# Controlador_de_corriente_V3.net
KiCad netlist of a schematic drawn in Altium Designer
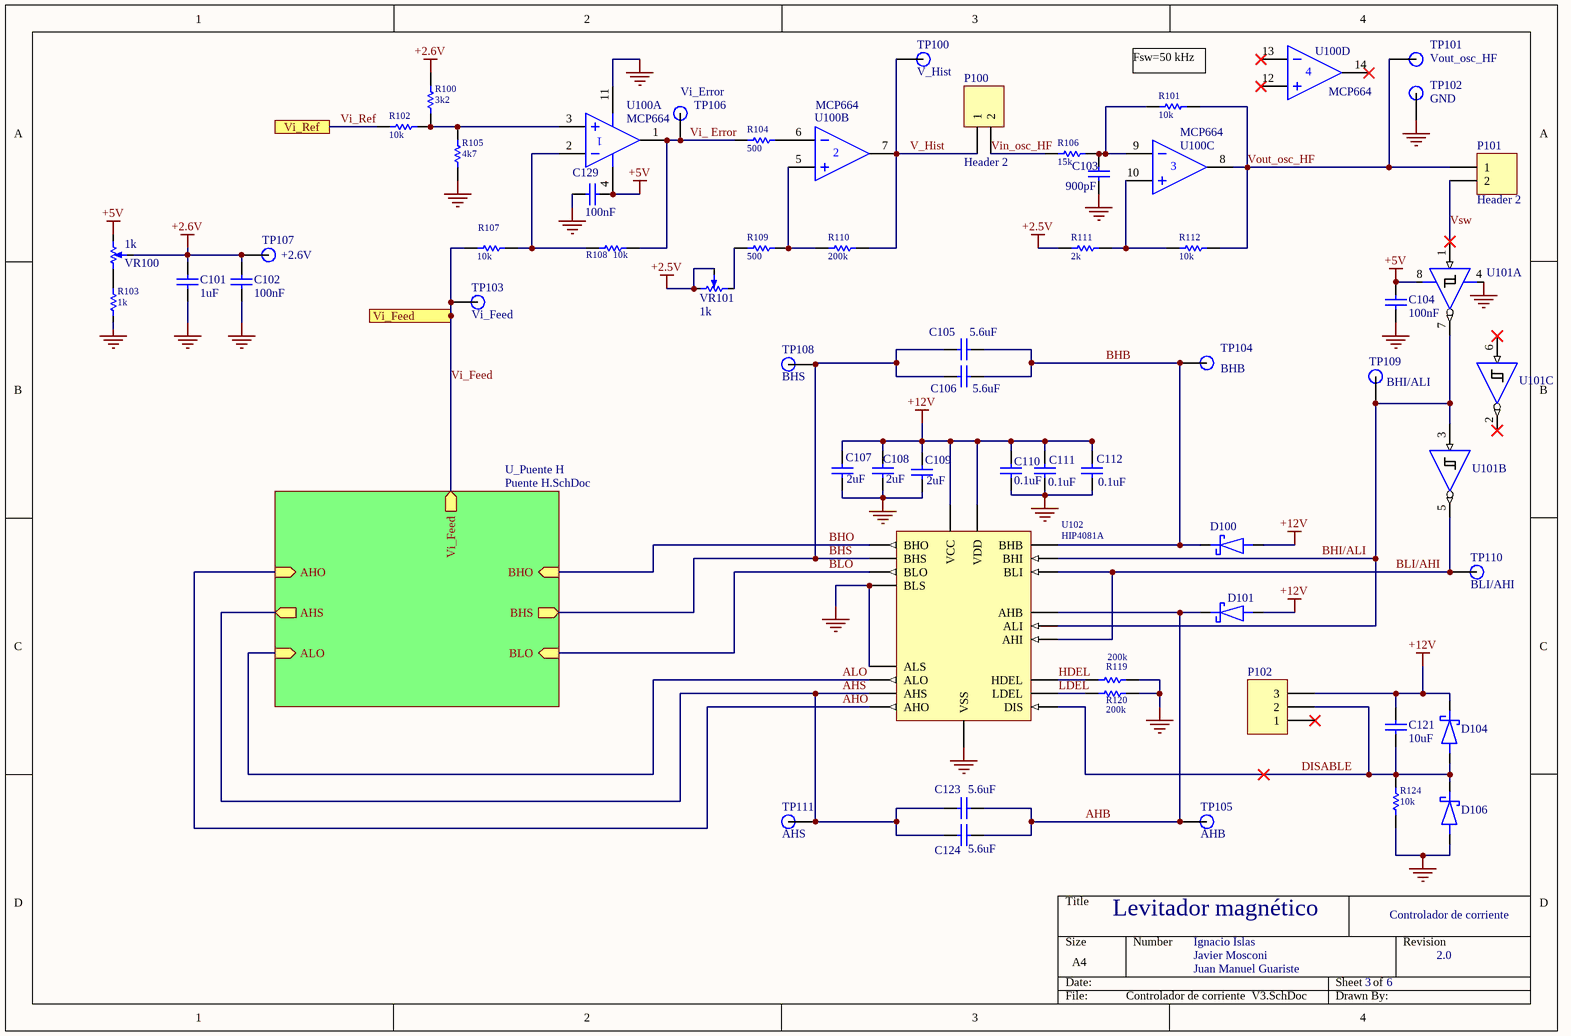
[diagram p0: Controlador de corriente  V3.SchDoc]

(export (version "E")
  (design (tool "Eeschema 10.0.6"))
  (components
    (comp (ref "C101")
      (value "1uF")
      (footprint "C1206")
      (description "CAP CER 1UF 25V X7R 1206")
      (fields (field (name "MANUFACTURER") "CAL-CHIP ELECTRONICS, INC.") (field (name "Comment") "Capacitor"))
      (libsource (lib "Levitador_GMI") (part "Capacitor"))
    )
    (comp (ref "C102")
      (value "100nF")
      (footprint "C1206")
      (description "CAP CER 0.1UF 50V X7R 1206")
      (fields (field (name "MANUFACTURER") "Venkel") (field (name "Comment") "Capacitor"))
      (libsource (lib "Levitador_GMI") (part "Capacitor"))
    )
    (comp (ref "C103")
      (value "900pF")
      (footprint "C1206")
      (description "CAP CER 910PF 50V NP0 1206")
      (fields (field (name "MANUFACTURER") "KEMET") (field (name "Comment") "Capacitor"))
      (libsource (lib "Levitador_GMI") (part "Capacitor"))
    )
    (comp (ref "C104")
      (value "100nF")
      (footprint "C1206")
      (description "CAP CER 0.1UF 50V X7R 1206")
      (fields (field (name "MANUFACTURER") "Venkel") (field (name "Comment") "Capacitor"))
      (libsource (lib "Levitador_GMI") (part "Capacitor"))
    )
    (comp (ref "C105")
      (value "5.6uF")
      (footprint "C1206")
      (description "CAP CER 4.7UF 50V X7R 1206")
      (fields (field (name "MANUFACTURER") "Samsung Electro-Mechanics") (field (name "Comment") "Capacitor"))
      (libsource (lib "Levitador_GMI") (part "Capacitor"))
    )
    (comp (ref "C106")
      (value "5.6uF")
      (footprint "C1206")
      (description "CAP CER 4.7UF 50V X7R 1206")
      (fields (field (name "MANUFACTURER") "Samsung Electro-Mechanics") (field (name "Comment") "Capacitor"))
      (libsource (lib "Levitador_GMI") (part "Capacitor"))
    )
    (comp (ref "C107")
      (value "2uF")
      (footprint "C1206")
      (description "CAP1206 X5R 2.2UF 20% 35V")
      (fields (field (name "MANUFACTURER") "CAL-CHIP ELECTRONICS, INC.") (field (name "Comment") "Capacitor"))
      (libsource (lib "Levitador_GMI") (part "Capacitor"))
    )
    (comp (ref "C108")
      (value "2uF")
      (footprint "C1206")
      (description "CAP1206 X5R 2.2UF 20% 35V")
      (fields (field (name "MANUFACTURER") "CAL-CHIP ELECTRONICS, INC.") (field (name "Comment") "Capacitor"))
      (libsource (lib "Levitador_GMI") (part "Capacitor"))
    )
    (comp (ref "C109")
      (value "2uF")
      (footprint "C1206")
      (description "CAP1206 X5R 2.2UF 20% 35V")
      (fields (field (name "MANUFACTURER") "CAL-CHIP ELECTRONICS, INC.") (field (name "Comment") "Capacitor"))
      (libsource (lib "Levitador_GMI") (part "Capacitor"))
    )
    (comp (ref "C110")
      (value "0.1uF")
      (footprint "C1206")
      (description "CAP CER 0.1UF 50V X7R 1206")
      (fields (field (name "MANUFACTURER") "Venkel") (field (name "Comment") "Capacitor"))
      (libsource (lib "Levitador_GMI") (part "Capacitor"))
    )
    (comp (ref "C111")
      (value "0.1uF")
      (footprint "C1206")
      (description "CAP CER 0.1UF 50V X7R 1206")
      (fields (field (name "MANUFACTURER") "Venkel") (field (name "Comment") "Capacitor"))
      (libsource (lib "Levitador_GMI") (part "Capacitor"))
    )
    (comp (ref "C112")
      (value "0.1uF")
      (footprint "C1206")
      (description "CAP CER 0.1UF 50V X7R 1206")
      (fields (field (name "MANUFACTURER") "Venkel") (field (name "Comment") "Capacitor"))
      (libsource (lib "Levitador_GMI") (part "Capacitor"))
    )
    (comp (ref "C121")
      (value "10uF")
      (footprint "C1206")
      (description "CAP CER 10UF 16V X7R 1206")
      (fields (field (name "MANUFACTURER") "CAL-CHIP ELECTRONICS, INC.") (field (name "Comment") "Capacitor"))
      (libsource (lib "Levitador_GMI") (part "Capacitor"))
    )
    (comp (ref "C123")
      (value "5.6uF")
      (footprint "C1206")
      (description "CAP CER 4.7UF 50V X7R 1206")
      (fields (field (name "MANUFACTURER") "Samsung Electro-Mechanics") (field (name "Comment") "Capacitor"))
      (libsource (lib "Levitador_GMI") (part "Capacitor"))
    )
    (comp (ref "C124")
      (value "5.6uF")
      (footprint "C1206")
      (description "CAP CER 4.7UF 50V X7R 1206")
      (fields (field (name "MANUFACTURER") "Samsung Electro-Mechanics") (field (name "Comment") "Capacitor"))
      (libsource (lib "Levitador_GMI") (part "Capacitor"))
    )
    (comp (ref "C129")
      (value "100nF")
      (footprint "C1206")
      (description "CAP CER 0.1UF 50V X7R 1206")
      (fields (field (name "MANUFACTURER") "Venkel") (field (name "Comment") "Capacitor"))
      (libsource (lib "Levitador_GMI") (part "Capacitor"))
    )
    (comp (ref "D100")
      (value "RSX205LAM30TR")
      (footprint "SODFL4725X105N")
      (description "DIODE SCHOTTKY 30V 2A PMDTM")
      (libsource (lib "Levitador_GMI") (part "RSX205LAM30TR"))
    )
    (comp (ref "D101")
      (value "RSX205LAM30TR")
      (footprint "SODFL4725X105N")
      (description "DIODE SCHOTTKY 30V 2A PMDTM")
      (libsource (lib "Levitador_GMI") (part "RSX205LAM30TR"))
    )
    (comp (ref "D104")
      (value "RSX205LAM30TR")
      (footprint "SODFL4725X105N")
      (description "DIODE SCHOTTKY 30V 2A PMDTM")
      (libsource (lib "Levitador_GMI") (part "RSX205LAM30TR"))
    )
    (comp (ref "D106")
      (value "RSX205LAM30TR")
      (footprint "SODFL4725X105N")
      (description "DIODE SCHOTTKY 30V 2A PMDTM")
      (libsource (lib "Levitador_GMI") (part "RSX205LAM30TR"))
    )
    (comp (ref "P100")
      (value "Header 2")
      (footprint "HDR1X2")
      (description "TERM BLK 2P SIDE ENT 2.54MM PCB")
      (fields (field (name "MANUFACTURER") "TE Connectivity AMP Connectors"))
      (libsource (lib "") (part "Header 2_1"))
    )
    (comp (ref "P101")
      (value "Header 2")
      (footprint "HDR1X2")
      (description "TERM BLK 2P SIDE ENT 2.54MM PCB")
      (fields (field (name "MANUFACTURER") "TE Connectivity AMP Connectors"))
      (libsource (lib "Levitador_GMI") (part "Header 2"))
    )
    (comp (ref "P102")
      (value "Header 3")
      (footprint "HDR1X3")
      (description "TERM BLK 3P SIDE ENT 2.54MM PCB")
      (fields (field (name "MANUFACTURER") "TE Connectivity AMP Connectors"))
      (libsource (lib "Levitador_GMI") (part "Header 3"))
    )
    (comp (ref "R100")
      (value "3k2")
      (footprint "Levitador_GMI:R1206")
      (description "RES 3.2K OHM 1% 1/4W 1206")
      (fields (field (name "MANUFACTURER") "KOA Speer Electronics, Inc.") (field (name "TOLERANCE") "1%"))
      (libsource (lib "Levitador_GMI") (part "R1206"))
    )
    (comp (ref "R101")
      (value "10k")
      (footprint "Levitador_GMI:R1206")
      (description "RES 10K OHM 1% 1/4W 1206")
      (fields (field (name "MANUFACTURER") "YAGEO") (field (name "TOLERANCE") "1%"))
      (libsource (lib "Levitador_GMI") (part "R1206"))
    )
    (comp (ref "R102")
      (value "10k")
      (footprint "Levitador_GMI:R1206")
      (description "RES 10K OHM 1% 1/4W 1206")
      (fields (field (name "MANUFACTURER") "YAGEO") (field (name "TOLERANCE") "1%"))
      (libsource (lib "Levitador_GMI") (part "R1206"))
    )
    (comp (ref "R103")
      (value "1k")
      (footprint "Levitador_GMI:R1206")
      (description "Resistor Chip; 1/8W;")
      (fields (field (name "MANUFACTURER") "Stackpole Electronics Inc") (field (name "TOLERANCE") "1%"))
      (libsource (lib "Levitador_GMI") (part "R1206"))
    )
    (comp (ref "R104")
      (value "500")
      (footprint "Levitador_GMI:R1206")
      (description "RES SMD 500 OHM 0.1% 0.3W 1206")
      (fields
        (field (name "MANUFACTURER") "Vishay Foil Resistors (Division of Vishay Precision Group)")
        (field (name "TOLERANCE") "0.1%")
      )
      (libsource (lib "Levitador_GMI") (part "R1206"))
    )
    (comp (ref "R105")
      (value "4k7")
      (footprint "Levitador_GMI:R1206")
      (description "RES 4.7K OHM 1% 1/4W 1206")
      (fields (field (name "MANUFACTURER") "Stackpole Electronics Inc") (field (name "TOLERANCE") "1%"))
      (libsource (lib "Levitador_GMI") (part "R1206"))
    )
    (comp (ref "R106")
      (value "15k")
      (footprint "Levitador_GMI:R1206")
      (description "RES 15K OHM 1% 1/4W 1206")
      (fields (field (name "MANUFACTURER") "Vishay Dale") (field (name "TOLERANCE") "1%"))
      (libsource (lib "Levitador_GMI") (part "R1206"))
    )
    (comp (ref "R107")
      (value "10k")
      (footprint "Levitador_GMI:R1206")
      (description "RES 10K OHM 1% 1/4W 1206")
      (fields (field (name "MANUFACTURER") "YAGEO") (field (name "TOLERANCE") "1%"))
      (libsource (lib "Levitador_GMI") (part "R1206"))
    )
    (comp (ref "R108")
      (value "10k")
      (footprint "Levitador_GMI:R1206")
      (description "RES 10K OHM 1% 1/4W 1206")
      (fields (field (name "MANUFACTURER") "YAGEO") (field (name "TOLERANCE") "1%"))
      (libsource (lib "Levitador_GMI") (part "R1206"))
    )
    (comp (ref "R109")
      (value "500")
      (footprint "Levitador_GMI:R1206")
      (description "RES SMD 500 OHM 0.1% 0.3W 1206")
      (fields
        (field (name "MANUFACTURER") "Vishay Foil Resistors (Division of Vishay Precision Group)")
        (field (name "TOLERANCE") "0.1%")
      )
      (libsource (lib "Levitador_GMI") (part "R1206"))
    )
    (comp (ref "R110")
      (value "200k")
      (footprint "Levitador_GMI:R1206")
      (description "RES 200K OHM 1% 1/4W 1206")
      (fields (field (name "MANUFACTURER") "YAGEO") (field (name "TOLERANCE") "1%"))
      (libsource (lib "Levitador_GMI") (part "R1206"))
    )
    (comp (ref "R111")
      (value "2k")
      (footprint "Levitador_GMI:R1206")
      (description "RES 2K OHM 1% 1/4W 1206")
      (fields (field (name "MANUFACTURER") "Stackpole Electronics Inc") (field (name "TOLERANCE") "1%"))
      (libsource (lib "Levitador_GMI") (part "R1206"))
    )
    (comp (ref "R112")
      (value "10k")
      (footprint "Levitador_GMI:R1206")
      (description "RES 10K OHM 1% 1/4W 1206")
      (fields (field (name "MANUFACTURER") "YAGEO") (field (name "TOLERANCE") "1%"))
      (libsource (lib "Levitador_GMI") (part "R1206"))
    )
    (comp (ref "R119")
      (value "200k")
      (footprint "Levitador_GMI:R1206")
      (description "RES 200K OHM 1% 1/4W 1206")
      (fields (field (name "MANUFACTURER") "YAGEO") (field (name "TOLERANCE") "1%"))
      (libsource (lib "Levitador_GMI") (part "R1206"))
    )
    (comp (ref "R120")
      (value "200k")
      (footprint "Levitador_GMI:R1206")
      (description "RES 200K OHM 1% 1/4W 1206")
      (fields (field (name "MANUFACTURER") "YAGEO") (field (name "TOLERANCE") "1%"))
      (libsource (lib "Levitador_GMI") (part "R1206"))
    )
    (comp (ref "R124")
      (value "10k")
      (footprint "Levitador_GMI:R1206")
      (description "RES 10K OHM 1% 1/4W 1206")
      (fields (field (name "MANUFACTURER") "YAGEO") (field (name "TOLERANCE") "1%"))
      (libsource (lib "Levitador_GMI") (part "R1206"))
    )
    (comp (ref "TP100")
      (value "V_Hist")
      (footprint "TestPoint Keystone 5000 Silver-Red")
      (description "PC TEST POINT MINIATURE RED")
      (fields (field (name "MANUFACTURER") "Keystone Electronics"))
      (libsource (lib "Levitador_GMI") (part "Testpoint"))
    )
    (comp (ref "TP101")
      (value "Vout_osc_HF")
      (footprint "TestPoint Keystone 5000 Silver-Red")
      (description "PC TEST POINT MINIATURE RED")
      (fields (field (name "MANUFACTURER") "Keystone Electronics"))
      (libsource (lib "Levitador_GMI") (part "Testpoint"))
    )
    (comp (ref "TP102")
      (value "GND")
      (footprint "TestPoint Keystone 5000 Silver-Red")
      (description "PC TEST POINT MINIATURE RED")
      (fields (field (name "MANUFACTURER") "Keystone Electronics"))
      (libsource (lib "Levitador_GMI") (part "Testpoint"))
    )
    (comp (ref "TP103")
      (value "Vi_Feed")
      (footprint "TestPoint Keystone 5000 Silver-Red")
      (description "PC TEST POINT MINIATURE RED")
      (fields (field (name "MANUFACTURER") "Keystone Electronics"))
      (libsource (lib "Levitador_GMI") (part "Testpoint"))
    )
    (comp (ref "TP104")
      (value "BHB")
      (footprint "TestPoint Keystone 5000 Silver-Red")
      (description "PC TEST POINT MINIATURE RED")
      (fields (field (name "MANUFACTURER") "Keystone Electronics"))
      (libsource (lib "Levitador_GMI") (part "Testpoint"))
    )
    (comp (ref "TP105")
      (value "AHB")
      (footprint "TestPoint Keystone 5000 Silver-Red")
      (description "PC TEST POINT MINIATURE RED")
      (fields (field (name "MANUFACTURER") "Keystone Electronics"))
      (libsource (lib "Levitador_GMI") (part "Testpoint"))
    )
    (comp (ref "TP106")
      (value "Vi_Error")
      (footprint "TestPoint Keystone 5000 Silver-Red")
      (description "PC TEST POINT MINIATURE RED")
      (fields (field (name "MANUFACTURER") "Keystone Electronics"))
      (libsource (lib "Levitador_GMI") (part "Testpoint"))
    )
    (comp (ref "TP107")
      (value "+2.6V")
      (footprint "TestPoint Keystone 5000 Silver-Red")
      (description "PC TEST POINT MINIATURE RED")
      (fields (field (name "MANUFACTURER") "Keystone Electronics"))
      (libsource (lib "Levitador_GMI") (part "Testpoint"))
    )
    (comp (ref "TP108")
      (value "BHS")
      (footprint "TestPoint Keystone 5000 Silver-Red")
      (description "PC TEST POINT MINIATURE RED")
      (fields (field (name "MANUFACTURER") "Keystone Electronics"))
      (libsource (lib "Levitador_GMI") (part "Testpoint"))
    )
    (comp (ref "TP109")
      (value "BHI/ALI")
      (footprint "TestPoint Keystone 5000 Silver-Red")
      (description "PC TEST POINT MINIATURE RED")
      (fields (field (name "MANUFACTURER") "Keystone Electronics"))
      (libsource (lib "Levitador_GMI") (part "Testpoint"))
    )
    (comp (ref "TP110")
      (value "BLI/AHI")
      (footprint "TestPoint Keystone 5000 Silver-Red")
      (description "PC TEST POINT MINIATURE RED")
      (fields (field (name "MANUFACTURER") "Keystone Electronics"))
      (libsource (lib "Levitador_GMI") (part "Testpoint"))
    )
    (comp (ref "TP111")
      (value "AHS")
      (footprint "TestPoint Keystone 5000 Silver-Red")
      (description "PC TEST POINT MINIATURE RED")
      (fields (field (name "MANUFACTURER") "Keystone Electronics"))
      (libsource (lib "Levitador_GMI") (part "Testpoint"))
    )
    (comp (ref "U100")
      (value "MCP664")
      (footprint "SOIC14")
      (description "IC OPAMP GP 4 CIRCUIT 14TSSOP")
      (fields (field (name "MANUFACTURER") "Microchip Technology"))
      (libsource (lib "Levitador_GMI") (part "MCP664"))
    )
    (comp (ref "U101")
      (value "SN74LVC3G06DCUT")
      (footprint "SOP50P310X90-8N")
      (description "IC INVERTER OD 3CH 3-INP 8VSSOP")
      (fields (field (name "MANUFACTURER") "Texas Instruments"))
      (libsource (lib "Levitador_GMI") (part "SN74LVC3G06DCUT"))
    )
    (comp (ref "U102")
      (value "HIP4081A")
      (footprint "SOIC20")
      (description "IC GATE DRVR HALF-BRIDGE 20SOIC")
      (fields (field (name "MANUFACTURER") "Renesas Electronics America Inc"))
      (libsource (lib "Levitador_GMI") (part "HIP4081A"))
    )
    (comp (ref "VR100")
      (value "1k")
      (footprint "3299Y1203LF")
      (description "e")
      (fields (field (name "MANUFACTURER") "Bourns Inc.") (field (name "Comment") "Trimmer (Thru-Hole)"))
      (libsource (lib "Levitador_GMI") (part "Trimmer"))
    )
    (comp (ref "VR101")
      (value "1k")
      (footprint "3299Y1203LF")
      (description "TRIMMER 1K OHM 0.5W PC PIN TOP")
      (fields (field (name "MANUFACTURER") "Bourns Inc.") (field (name "Comment") "Trimmer (Thru-Hole)"))
      (libsource (lib "Levitador_GMI") (part "Trimmer"))
    )
  )
  (nets
    (net (code "1") (name "+2.5V") (class "Default")
      (node (ref "R111") (pin "2") (pinfunction "2_2") (pintype "passive"))
      (node (ref "VR101") (pin "1") (pinfunction "CCW_1") (pintype "passive"))
      (node (ref "VR101") (pin "2") (pinfunction "W_2") (pintype "passive"))
    )
    (net (code "2") (name "+2.6V") (class "Default")
      (node (ref "C101") (pin "2") (pinfunction "2_2") (pintype "passive"))
      (node (ref "C102") (pin "2") (pinfunction "2_2") (pintype "passive"))
      (node (ref "R100") (pin "2") (pinfunction "2_2") (pintype "passive"))
      (node (ref "TP107") (pin "1") (pinfunction "1_1") (pintype "passive"))
      (node (ref "VR100") (pin "2") (pinfunction "W_2") (pintype "passive"))
    )
    (net (code "3") (name "+5V") (class "Default")
      (node (ref "C104") (pin "2") (pinfunction "2_2") (pintype "passive"))
      (node (ref "C129") (pin "2") (pinfunction "2_2") (pintype "passive"))
      (node (ref "U100") (pin "4") (pinfunction "V+_4") (pintype "power_in"))
      (node (ref "U101") (pin "8") (pinfunction "Vcc_8") (pintype "power_in"))
      (node (ref "VR100") (pin "1") (pinfunction "CCW_1") (pintype "passive"))
    )
    (net (code "4") (name "+12V") (class "Default")
      (node (ref "C107") (pin "2") (pinfunction "2_2") (pintype "passive"))
      (node (ref "C108") (pin "2") (pinfunction "2_2") (pintype "passive"))
      (node (ref "C109") (pin "2") (pinfunction "2_2") (pintype "passive"))
      (node (ref "C110") (pin "2") (pinfunction "2_2") (pintype "passive"))
      (node (ref "C111") (pin "2") (pinfunction "2_2") (pintype "passive"))
      (node (ref "C112") (pin "2") (pinfunction "2_2") (pintype "passive"))
      (node (ref "C121") (pin "2") (pinfunction "2_2") (pintype "passive"))
      (node (ref "D100") (pin "2") (pinfunction "A_2") (pintype "passive"))
      (node (ref "D101") (pin "2") (pinfunction "A_2") (pintype "passive"))
      (node (ref "D104") (pin "1") (pinfunction "K_1") (pintype "passive"))
      (node (ref "P102") (pin "3") (pinfunction "3_3") (pintype "passive"))
      (node (ref "U102") (pin "15") (pinfunction "VCC_15") (pintype "power_in"))
      (node (ref "U102") (pin "16") (pinfunction "VDD_16") (pintype "power_in"))
    )
    (net (code "5") (name "/AHB") (class "Default")
      (node (ref "C123") (pin "2") (pinfunction "2_2") (pintype "passive"))
      (node (ref "C124") (pin "2") (pinfunction "2_2") (pintype "passive"))
      (node (ref "D101") (pin "1") (pinfunction "K_1") (pintype "passive"))
      (node (ref "TP105") (pin "1") (pinfunction "1_1") (pintype "passive"))
      (node (ref "U102") (pin "10") (pinfunction "AHB_10") (pintype "power_in"))
    )
    (net (code "6") (name "/AHO") (class "Default")
      (node (ref "U102") (pin "11") (pinfunction "AHO_11") (pintype "output"))
    )
    (net (code "7") (name "/AHS") (class "Default")
      (node (ref "C123") (pin "1") (pinfunction "1_1") (pintype "passive"))
      (node (ref "C124") (pin "1") (pinfunction "1_1") (pintype "passive"))
      (node (ref "TP111") (pin "1") (pinfunction "1_1") (pintype "passive"))
      (node (ref "U102") (pin "12") (pinfunction "AHS_12") (pintype "passive"))
    )
    (net (code "8") (name "/ALO") (class "Default")
      (node (ref "U102") (pin "13") (pinfunction "ALO_13") (pintype "output"))
    )
    (net (code "9") (name "/BHB") (class "Default")
      (node (ref "C105") (pin "2") (pinfunction "2_2") (pintype "passive"))
      (node (ref "C106") (pin "2") (pinfunction "2_2") (pintype "passive"))
      (node (ref "D100") (pin "1") (pinfunction "K_1") (pintype "passive"))
      (node (ref "TP104") (pin "1") (pinfunction "1_1") (pintype "passive"))
      (node (ref "U102") (pin "1") (pinfunction "BHB_1") (pintype "power_in"))
    )
    (net (code "10") (name "/BHI{slash}ALI") (class "Default")
      (node (ref "TP109") (pin "1") (pinfunction "1_1") (pintype "passive"))
      (node (ref "U101") (pin "3") (pinfunction "2A_3") (pintype "input"))
      (node (ref "U101") (pin "7") (pinfunction "1Y_7") (pintype "output"))
      (node (ref "U102") (pin "2") (pinfunction "BHI_2") (pintype "input"))
      (node (ref "U102") (pin "6") (pinfunction "ALI_6") (pintype "input"))
    )
    (net (code "11") (name "/BHO") (class "Default")
      (node (ref "U102") (pin "20") (pinfunction "BHO_20") (pintype "output"))
    )
    (net (code "12") (name "/BHS") (class "Default")
      (node (ref "C105") (pin "1") (pinfunction "1_1") (pintype "passive"))
      (node (ref "C106") (pin "1") (pinfunction "1_1") (pintype "passive"))
      (node (ref "TP108") (pin "1") (pinfunction "1_1") (pintype "passive"))
      (node (ref "U102") (pin "19") (pinfunction "BHS_19") (pintype "passive"))
    )
    (net (code "13") (name "/BLI{slash}AHI") (class "Default")
      (node (ref "TP110") (pin "1") (pinfunction "1_1") (pintype "passive"))
      (node (ref "U101") (pin "5") (pinfunction "2Y_5") (pintype "output"))
      (node (ref "U102") (pin "5") (pinfunction "BLI_5") (pintype "input"))
      (node (ref "U102") (pin "7") (pinfunction "AHI_7") (pintype "input"))
    )
    (net (code "14") (name "/BLO") (class "Default")
      (node (ref "U102") (pin "18") (pinfunction "BLO_18") (pintype "output"))
    )
    (net (code "15") (name "/DISABLE") (class "Default")
      (node (ref "C121") (pin "1") (pinfunction "1_1") (pintype "passive"))
      (node (ref "D104") (pin "2") (pinfunction "A_2") (pintype "passive"))
      (node (ref "D106") (pin "1") (pinfunction "K_1") (pintype "passive"))
      (node (ref "P102") (pin "2") (pinfunction "2_2") (pintype "passive"))
      (node (ref "R124") (pin "2") (pinfunction "2_2") (pintype "passive"))
      (node (ref "U102") (pin "3") (pinfunction "DIS_3") (pintype "input"))
    )
    (net (code "16") (name "/HDEL") (class "Default")
      (node (ref "R119") (pin "1") (pinfunction "1_1") (pintype "passive"))
      (node (ref "U102") (pin "8") (pinfunction "HDEL_8") (pintype "passive"))
    )
    (net (code "17") (name "/LDEL") (class "Default")
      (node (ref "R120") (pin "1") (pinfunction "1_1") (pintype "passive"))
      (node (ref "U102") (pin "9") (pinfunction "LDEL_9") (pintype "passive"))
    )
    (net (code "18") (name "/V_Hist") (class "Default")
      (node (ref "P100") (pin "1") (pinfunction "1_1") (pintype "passive"))
      (node (ref "R110") (pin "2") (pinfunction "2_2") (pintype "passive"))
      (node (ref "TP100") (pin "1") (pinfunction "1_1") (pintype "passive"))
      (node (ref "U100") (pin "7") (pinfunction "OUT_7") (pintype "passive"))
    )
    (net (code "19") (name "/Vi_ Error") (class "Default")
      (node (ref "R104") (pin "1") (pinfunction "1_1") (pintype "passive"))
      (node (ref "R108") (pin "2") (pinfunction "2_2") (pintype "passive"))
      (node (ref "TP106") (pin "1") (pinfunction "1_1") (pintype "passive"))
      (node (ref "U100") (pin "1") (pinfunction "OUT_1") (pintype "passive"))
    )
    (net (code "20") (name "/Vi_Feed") (class "Default")
      (node (ref "R107") (pin "1") (pinfunction "1_1") (pintype "passive"))
      (node (ref "TP103") (pin "1") (pinfunction "1_1") (pintype "passive"))
    )
    (net (code "21") (name "/Vi_Ref") (class "Default")
      (node (ref "R102") (pin "1") (pinfunction "1_1") (pintype "passive"))
    )
    (net (code "22") (name "/Vin_osc_HF") (class "Default")
      (node (ref "P100") (pin "2") (pinfunction "2_2") (pintype "passive"))
      (node (ref "R106") (pin "1") (pinfunction "1_1") (pintype "passive"))
    )
    (net (code "23") (name "/Vout_osc_HF") (class "Default")
      (node (ref "P101") (pin "1") (pinfunction "1_1") (pintype "passive"))
      (node (ref "R101") (pin "2") (pinfunction "2_2") (pintype "passive"))
      (node (ref "R112") (pin "2") (pinfunction "2_2") (pintype "passive"))
      (node (ref "TP101") (pin "1") (pinfunction "1_1") (pintype "passive"))
      (node (ref "U100") (pin "8") (pinfunction "OUT_8") (pintype "passive"))
    )
    (net (code "24") (name "/Vsw") (class "Default")
      (node (ref "P101") (pin "2") (pinfunction "2_2") (pintype "passive"))
      (node (ref "U101") (pin "1") (pinfunction "1A_1") (pintype "input"))
    )
    (net (code "25") (name "GND") (class "Default")
      (node (ref "C101") (pin "1") (pinfunction "1_1") (pintype "passive"))
      (node (ref "C102") (pin "1") (pinfunction "1_1") (pintype "passive"))
      (node (ref "C103") (pin "2") (pinfunction "2_2") (pintype "passive"))
      (node (ref "C104") (pin "1") (pinfunction "1_1") (pintype "passive"))
      (node (ref "C107") (pin "1") (pinfunction "1_1") (pintype "passive"))
      (node (ref "C108") (pin "1") (pinfunction "1_1") (pintype "passive"))
      (node (ref "C109") (pin "1") (pinfunction "1_1") (pintype "passive"))
      (node (ref "C110") (pin "1") (pinfunction "1_1") (pintype "passive"))
      (node (ref "C111") (pin "1") (pinfunction "1_1") (pintype "passive"))
      (node (ref "C112") (pin "1") (pinfunction "1_1") (pintype "passive"))
      (node (ref "C129") (pin "1") (pinfunction "1_1") (pintype "passive"))
      (node (ref "D106") (pin "2") (pinfunction "A_2") (pintype "passive"))
      (node (ref "R103") (pin "1") (pinfunction "1_1") (pintype "passive"))
      (node (ref "R105") (pin "1") (pinfunction "1_1") (pintype "passive"))
      (node (ref "R119") (pin "2") (pinfunction "2_2") (pintype "passive"))
      (node (ref "R120") (pin "2") (pinfunction "2_2") (pintype "passive"))
      (node (ref "R124") (pin "1") (pinfunction "1_1") (pintype "passive"))
      (node (ref "TP102") (pin "1") (pinfunction "1_1") (pintype "passive"))
      (node (ref "U100") (pin "11") (pinfunction "V-_11") (pintype "power_in"))
      (node (ref "U101") (pin "4") (pinfunction "GND_4") (pintype "power_in"))
      (node (ref "U102") (pin "14") (pinfunction "ALS_14") (pintype "passive"))
      (node (ref "U102") (pin "17") (pinfunction "BLS_17") (pintype "passive"))
      (node (ref "U102") (pin "4") (pinfunction "VSS_4") (pintype "power_in"))
    )
    (net (code "26") (name "Net-(U100A-IN+)") (class "Default")
      (node (ref "R100") (pin "1") (pinfunction "1_1") (pintype "passive"))
      (node (ref "R102") (pin "2") (pinfunction "2_2") (pintype "passive"))
      (node (ref "R105") (pin "2") (pinfunction "2_2") (pintype "passive"))
      (node (ref "U100") (pin "3") (pinfunction "IN+_3") (pintype "passive"))
    )
    (net (code "27") (name "Net-(U100A-IN-)") (class "Default")
      (node (ref "R107") (pin "2") (pinfunction "2_2") (pintype "passive"))
      (node (ref "R108") (pin "1") (pinfunction "1_1") (pintype "passive"))
      (node (ref "U100") (pin "2") (pinfunction "IN-_2") (pintype "passive"))
    )
    (net (code "28") (name "Net-(U100B-IN+)") (class "Default")
      (node (ref "R109") (pin "1") (pinfunction "1_1") (pintype "passive"))
      (node (ref "R110") (pin "1") (pinfunction "1_1") (pintype "passive"))
      (node (ref "U100") (pin "5") (pinfunction "IN+_5") (pintype "passive"))
    )
    (net (code "29") (name "Net-(U100B-IN-)") (class "Default")
      (node (ref "R104") (pin "2") (pinfunction "2_2") (pintype "passive"))
      (node (ref "U100") (pin "6") (pinfunction "IN-_6") (pintype "passive"))
    )
    (net (code "30") (name "Net-(U100C-IN+)") (class "Default")
      (node (ref "R111") (pin "1") (pinfunction "1_1") (pintype "passive"))
      (node (ref "R112") (pin "1") (pinfunction "1_1") (pintype "passive"))
      (node (ref "U100") (pin "10") (pinfunction "IN+_10") (pintype "passive"))
    )
    (net (code "31") (name "Net-(U100C-IN-)") (class "Default")
      (node (ref "C103") (pin "1") (pinfunction "1_1") (pintype "passive"))
      (node (ref "R101") (pin "1") (pinfunction "1_1") (pintype "passive"))
      (node (ref "R106") (pin "2") (pinfunction "2_2") (pintype "passive"))
      (node (ref "U100") (pin "9") (pinfunction "IN-_9") (pintype "passive"))
    )
    (net (code "32") (name "Net-(VR100-CW)") (class "Default")
      (node (ref "R103") (pin "2") (pinfunction "2_2") (pintype "passive"))
      (node (ref "VR100") (pin "3") (pinfunction "CW_3") (pintype "passive"))
    )
    (net (code "33") (name "Net-(VR101-CW)") (class "Default")
      (node (ref "R109") (pin "2") (pinfunction "2_2") (pintype "passive"))
      (node (ref "VR101") (pin "3") (pinfunction "CW_3") (pintype "passive"))
    )
    (net (code "34") (name "unconnected-(P102-Pad1)") (class "Default")
      (node (ref "P102") (pin "1") (pinfunction "1_1") (pintype "passive+no_connect"))
    )
    (net (code "35") (name "unconnected-(U100D-IN+-Pad12)") (class "Default")
      (node (ref "U100") (pin "12") (pinfunction "IN+_12") (pintype "passive+no_connect"))
    )
    (net (code "36") (name "unconnected-(U100D-IN--Pad13)") (class "Default")
      (node (ref "U100") (pin "13") (pinfunction "IN-_13") (pintype "passive+no_connect"))
    )
    (net (code "37") (name "unconnected-(U100D-OUT-Pad14)") (class "Default")
      (node (ref "U100") (pin "14") (pinfunction "OUT_14") (pintype "passive+no_connect"))
    )
    (net (code "38") (name "unconnected-(U101C-3A-Pad6)") (class "Default")
      (node (ref "U101") (pin "6") (pinfunction "3A_6") (pintype "input+no_connect"))
    )
    (net (code "39") (name "unconnected-(U101C-3Y-Pad2)") (class "Default")
      (node (ref "U101") (pin "2") (pinfunction "3Y_2") (pintype "output+no_connect"))
    )
  )
)
